# Sheet3.net
KiCad netlist of a schematic drawn in Altium Designer
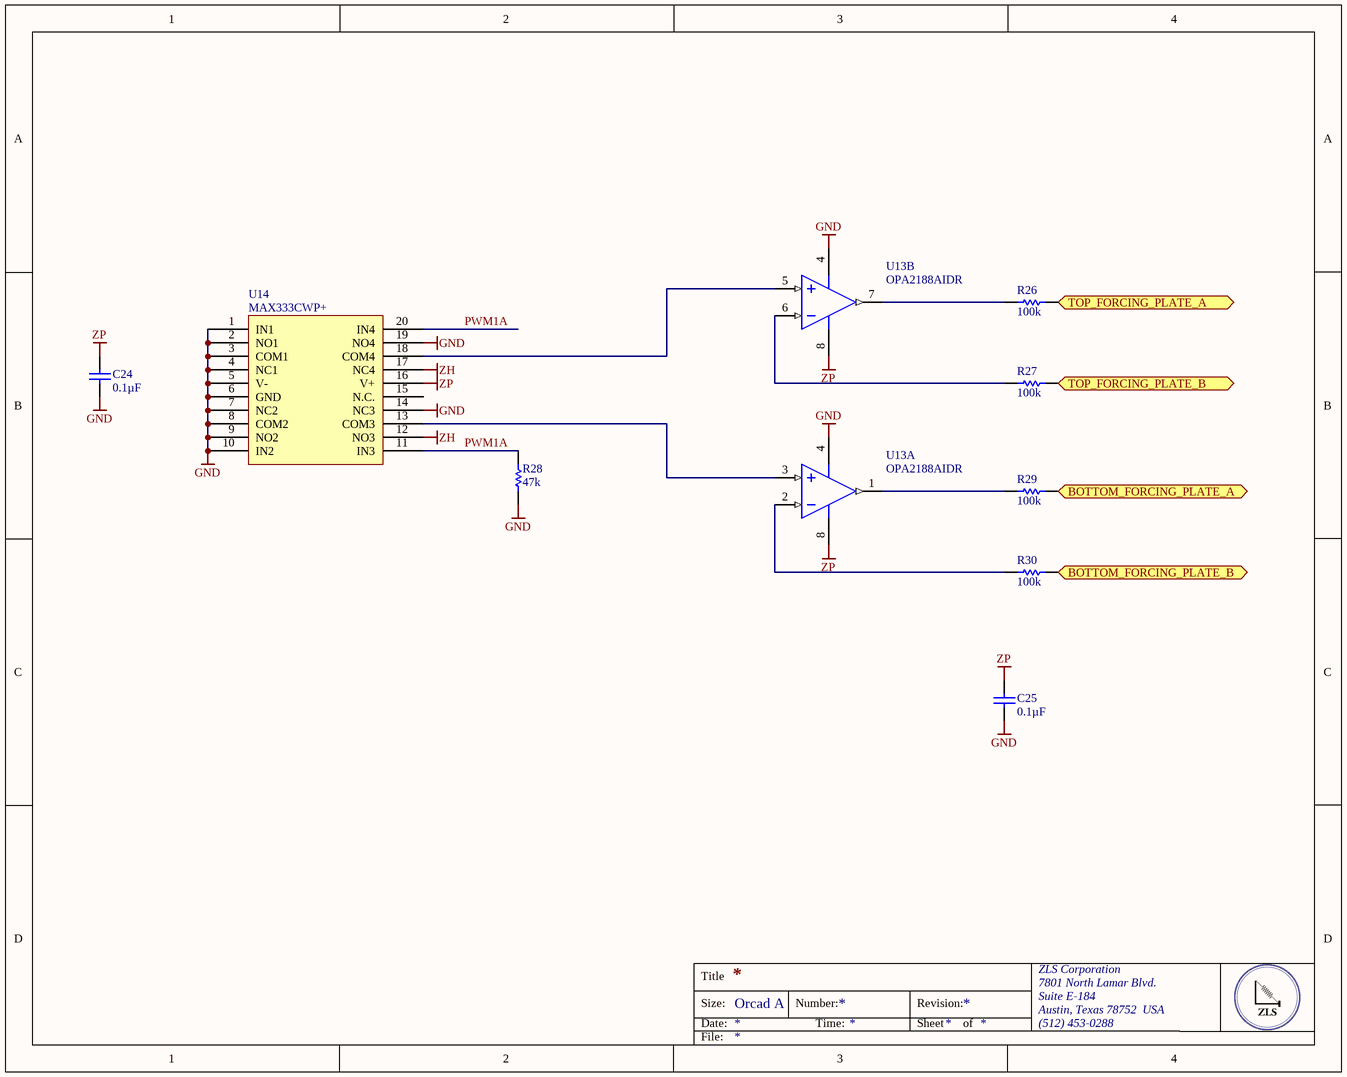
[diagram p0: Sheet3.SchDoc]

(export (version "E")
  (design (tool "Eeschema 10.0.6"))
  (components
    (comp (ref "C24")
      (value "CAP CER 0.1UF 25V X7R 0805")
      (footprint "CAPC0805(2012)145_N")
      (fields
        (field (name "MANUFACTURER") "Murata Electronics North America")
        (field (name "MANUFACTURER PART NUMBER") "GRM21BR71E104KA01L")
        (field (name "CAPACITANCE") "0.1µF")
        (field (name "TOLERANCE") "±10%")
      )
      (libsource (lib "Altium Content Vault") (part "CMP-1036-04795-1"))
    )
    (comp (ref "C25")
      (value "CAP CER 0.1UF 25V X7R 0805")
      (footprint "CAPC0805(2012)145_N")
      (fields
        (field (name "MANUFACTURER") "Murata Electronics North America")
        (field (name "MANUFACTURER PART NUMBER") "GRM21BR71E104KA01L")
        (field (name "CAPACITANCE") "0.1µF")
        (field (name "TOLERANCE") "±10%")
      )
      (libsource (lib "Altium Content Vault") (part "CMP-1036-04795-1"))
    )
    (comp (ref "R26")
      (value "100k")
      (footprint "RESC0402(1005)_M")
      (description "RES SMD 10K OHM 1% 1/8W 0402")
      (fields
        (field (name "MANUFACTURER") "Vishay Dale")
        (field (name "MANUFACTURER PART NUMBER") "CRCW0402100KFKEDHP")
      )
      (libsource (lib "Altium Content Vault") (part "CMP-1011-00651-1"))
    )
    (comp (ref "R27")
      (value "100k")
      (footprint "RESC0402(1005)_M")
      (description "RES SMD 10K OHM 1% 1/8W 0402")
      (fields
        (field (name "MANUFACTURER") "Vishay Dale")
        (field (name "MANUFACTURER PART NUMBER") "CRCW0402100KFKEDHP")
      )
      (libsource (lib "Altium Content Vault") (part "CMP-1011-00651-1"))
    )
    (comp (ref "R28")
      (value "47k")
      (footprint "RESC0402(1005)_M")
      (description "RES SMD 10K OHM 1% 1/8W 0402")
      (fields
        (field (name "MANUFACTURER") "Vishay Dale")
        (field (name "MANUFACTURER PART NUMBER") "CRCW0402100KFKEDHP")
      )
      (libsource (lib "Altium Content Vault") (part "CMP-1011-00651-1"))
    )
    (comp (ref "R29")
      (value "100k")
      (footprint "RESC0402(1005)_M")
      (description "RES SMD 10K OHM 1% 1/8W 0402")
      (fields
        (field (name "MANUFACTURER") "Vishay Dale")
        (field (name "MANUFACTURER PART NUMBER") "CRCW0402100KFKEDHP")
      )
      (libsource (lib "Altium Content Vault") (part "CMP-1011-00651-1"))
    )
    (comp (ref "R30")
      (value "100k")
      (footprint "RESC0402(1005)_M")
      (description "RES SMD 10K OHM 1% 1/8W 0402")
      (fields
        (field (name "MANUFACTURER") "Vishay Dale")
        (field (name "MANUFACTURER PART NUMBER") "CRCW0402100KFKEDHP")
      )
      (libsource (lib "Altium Content Vault") (part "CMP-1011-00651-1"))
    )
    (comp (ref "U13")
      (value "OPA2188AIDR")
      (footprint "D0008A_L")
      (fields (field (name "MANUFACTURER") "Texas Instruments"))
      (libsource (lib "Altium Content Vault") (part "CMP-0272-00241-3"))
    )
    (comp (ref "U14")
      (value "MAX333CWP+")
      (footprint "TSOP65P640X90-20N")
      (description "IC SWITCH QUAD SPDT 20TSSOP")
      (fields (field (name "MANUFACTURER") "Maxim") (field (name "MANUFACTURER PART NUMBER") "MAX333AEUP+"))
      (libsource (lib "ZLS_Schematic_lib") (part "MAX333CWP+"))
    )
  )
  (nets
    (net (code "1") (name "/BOTTOM_FORCING_PLATE_A") (class "Default")
      (node (ref "R29") (pin "1") (pinfunction "1_1") (pintype "passive"))
    )
    (net (code "2") (name "/BOTTOM_FORCING_PLATE_B") (class "Default")
      (node (ref "R30") (pin "1") (pinfunction "1_1") (pintype "passive"))
    )
    (net (code "3") (name "/PWM1A") (class "Default")
      (node (ref "R28") (pin "2") (pinfunction "2_2") (pintype "passive"))
      (node (ref "U14") (pin "11") (pinfunction "IN3_11") (pintype "passive"))
      (node (ref "U14") (pin "20") (pinfunction "IN4_20") (pintype "passive"))
    )
    (net (code "4") (name "/TOP_FORCING_PLATE_A") (class "Default")
      (node (ref "R26") (pin "1") (pinfunction "1_1") (pintype "passive"))
    )
    (net (code "5") (name "/TOP_FORCING_PLATE_B") (class "Default")
      (node (ref "R27") (pin "1") (pinfunction "1_1") (pintype "passive"))
    )
    (net (code "6") (name "GND") (class "Default")
      (node (ref "C24") (pin "1") (pinfunction "1_1") (pintype "passive"))
      (node (ref "C25") (pin "1") (pinfunction "1_1") (pintype "passive"))
      (node (ref "R28") (pin "1") (pinfunction "1_1") (pintype "passive"))
      (node (ref "U13") (pin "4") (pinfunction "V-_4") (pintype "power_in"))
      (node (ref "U14") (pin "1") (pinfunction "IN1_1") (pintype "passive"))
      (node (ref "U14") (pin "10") (pinfunction "IN2_10") (pintype "passive"))
      (node (ref "U14") (pin "14") (pinfunction "NC3_14") (pintype "passive"))
      (node (ref "U14") (pin "19") (pinfunction "NO4_19") (pintype "passive"))
      (node (ref "U14") (pin "2") (pinfunction "NO1_2") (pintype "passive"))
      (node (ref "U14") (pin "3") (pinfunction "COM1_3") (pintype "passive"))
      (node (ref "U14") (pin "4") (pinfunction "NC1_4") (pintype "passive"))
      (node (ref "U14") (pin "5") (pinfunction "V-_5") (pintype "power_in"))
      (node (ref "U14") (pin "6") (pinfunction "GND_6") (pintype "passive"))
      (node (ref "U14") (pin "7") (pinfunction "NC2_7") (pintype "passive"))
      (node (ref "U14") (pin "8") (pinfunction "COM2_8") (pintype "passive"))
      (node (ref "U14") (pin "9") (pinfunction "NO2_9") (pintype "passive"))
    )
    (net (code "7") (name "Net-(U13A-IN_A+)") (class "Default")
      (node (ref "U13") (pin "3") (pinfunction "IN_A+_3") (pintype "input"))
      (node (ref "U14") (pin "13") (pinfunction "COM3_13") (pintype "passive"))
    )
    (net (code "8") (name "Net-(U13A-IN_A-)") (class "Default")
      (node (ref "R30") (pin "2") (pinfunction "2_2") (pintype "passive"))
      (node (ref "U13") (pin "2") (pinfunction "IN_A-_2") (pintype "input"))
    )
    (net (code "9") (name "Net-(U13A-OUT_A)") (class "Default")
      (node (ref "R29") (pin "2") (pinfunction "2_2") (pintype "passive"))
      (node (ref "U13") (pin "1") (pinfunction "OUT_A_1") (pintype "output"))
    )
    (net (code "10") (name "Net-(U13B-IN_B+)") (class "Default")
      (node (ref "U13") (pin "5") (pinfunction "IN_B+_5") (pintype "input"))
      (node (ref "U14") (pin "18") (pinfunction "COM4_18") (pintype "passive"))
    )
    (net (code "11") (name "Net-(U13B-IN_B-)") (class "Default")
      (node (ref "R27") (pin "2") (pinfunction "2_2") (pintype "passive"))
      (node (ref "U13") (pin "6") (pinfunction "IN_B-_6") (pintype "input"))
    )
    (net (code "12") (name "Net-(U13B-OUT_B)") (class "Default")
      (node (ref "R26") (pin "2") (pinfunction "2_2") (pintype "passive"))
      (node (ref "U13") (pin "7") (pinfunction "OUT_B_7") (pintype "output"))
    )
    (net (code "13") (name "ZH") (class "Default")
      (node (ref "U14") (pin "12") (pinfunction "NO3_12") (pintype "passive"))
      (node (ref "U14") (pin "17") (pinfunction "NC4_17") (pintype "passive"))
    )
    (net (code "14") (name "ZP") (class "Default")
      (node (ref "C24") (pin "2") (pinfunction "2_2") (pintype "passive"))
      (node (ref "C25") (pin "2") (pinfunction "2_2") (pintype "passive"))
      (node (ref "U13") (pin "8") (pinfunction "V+_8") (pintype "power_in"))
      (node (ref "U14") (pin "16") (pinfunction "V+_16") (pintype "power_in"))
    )
    (net (code "15") (name "unconnected-(U14-N.C.-Pad15)") (class "Default")
      (node (ref "U14") (pin "15") (pinfunction "N.C._15") (pintype "passive"))
    )
  )
)
